# vco.net
KiCad netlist of a schematic drawn in EAGLE
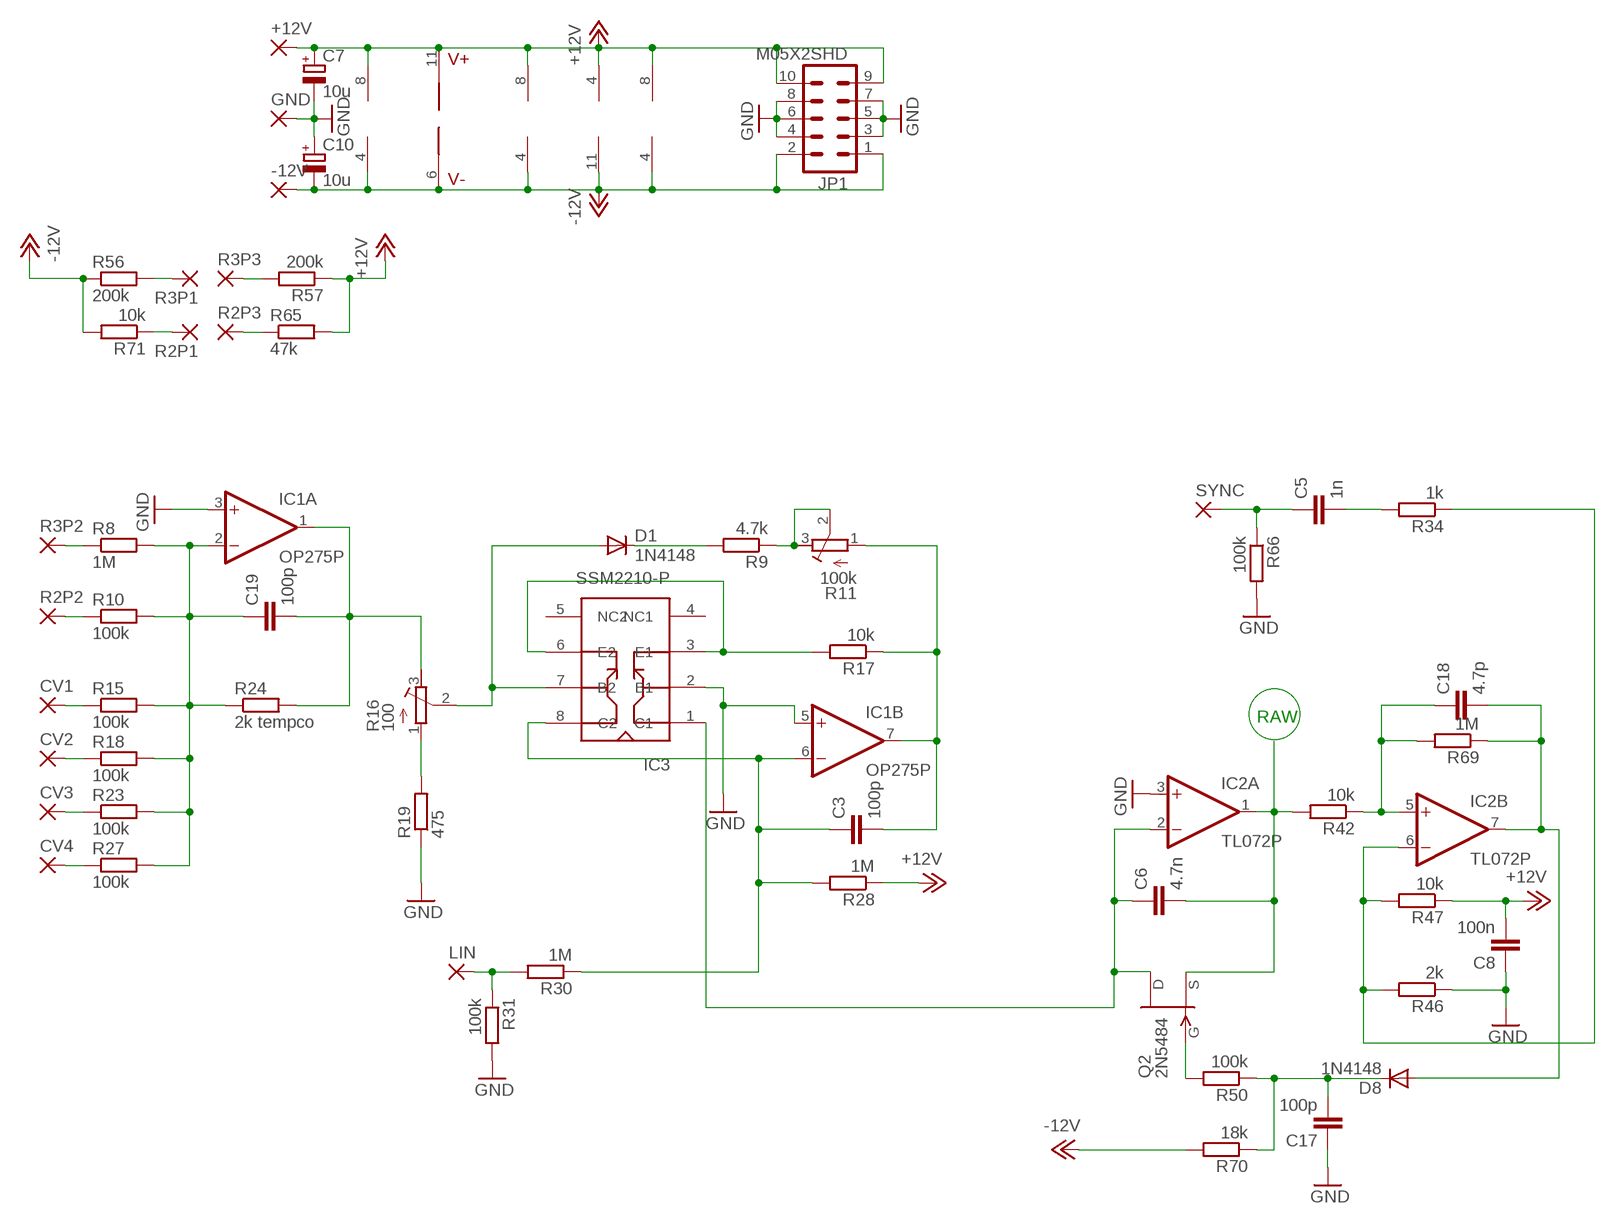
[diagram p0: schematic, sheet 1]
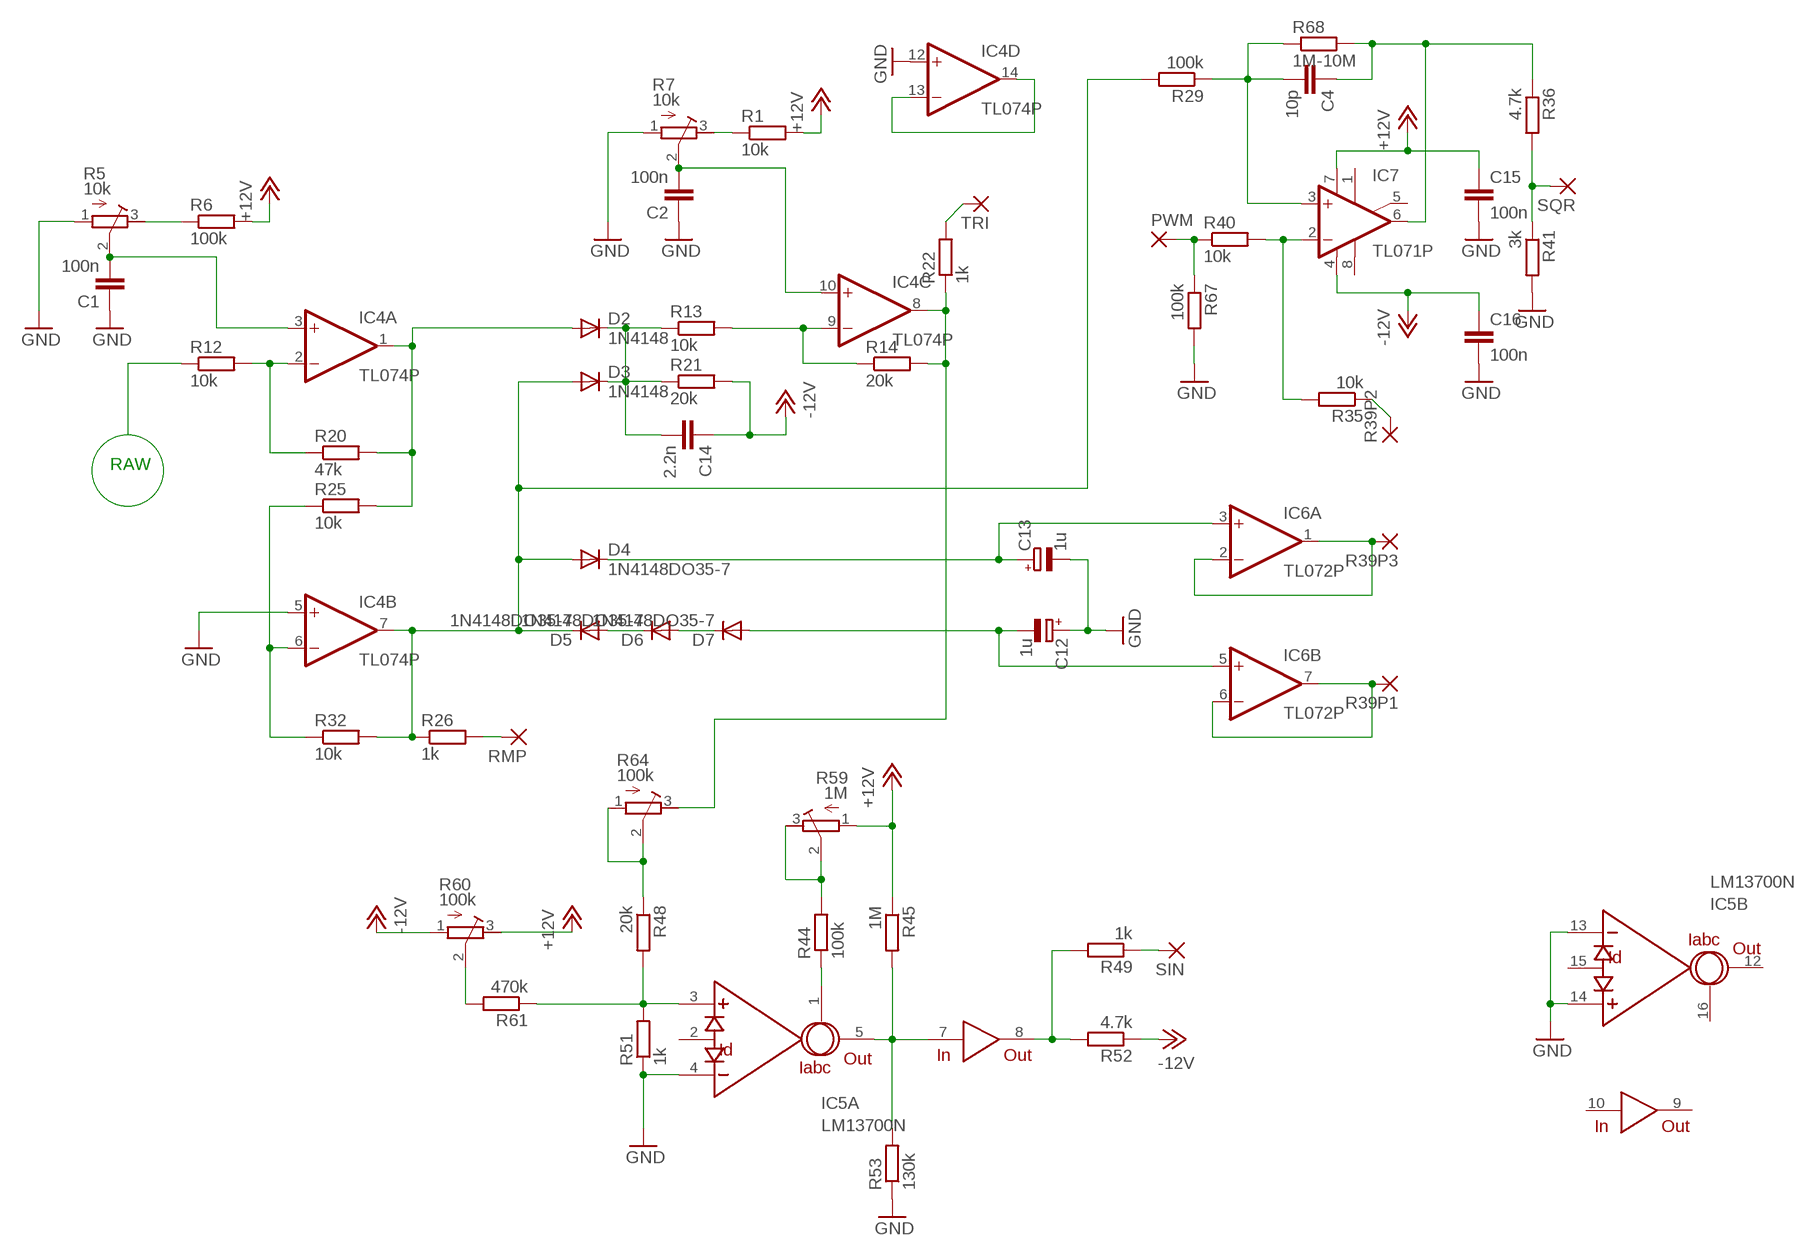
[diagram p1: schematic, sheet 2]

(export (version "E")
  (design (tool "Eeschema 10.0.6"))
  (components
    (comp (ref "C1")
      (value "100n")
      (footprint "eagle-import:C050-045X075")
      (libsource (lib "eagle-import") (part "C-EU050-045X075"))
    )
    (comp (ref "C2")
      (value "100n")
      (footprint "eagle-import:C050-045X075")
      (libsource (lib "eagle-import") (part "C-EU050-045X075"))
    )
    (comp (ref "C4")
      (value "10p")
      (footprint "eagle-import:C050-045X075")
      (libsource (lib "eagle-import") (part "C-EU050-045X075"))
    )
    (comp (ref "C12")
      (value "1u")
      (footprint "eagle-import:E2,5-7")
      (libsource (lib "eagle-import") (part "CPOL-EUE2.5-7"))
    )
    (comp (ref "C13")
      (value "1u")
      (footprint "eagle-import:E2,5-7")
      (libsource (lib "eagle-import") (part "CPOL-EUE2.5-7"))
    )
    (comp (ref "C14")
      (value "2.2n")
      (footprint "eagle-import:C050-045X075")
      (libsource (lib "eagle-import") (part "C-EU050-045X075"))
    )
    (comp (ref "C15")
      (value "100n")
      (footprint "eagle-import:C050-035X075")
      (libsource (lib "eagle-import") (part "C-EU050-035X075"))
    )
    (comp (ref "C16")
      (value "100n")
      (footprint "eagle-import:C050-035X075")
      (libsource (lib "eagle-import") (part "C-EU050-035X075"))
    )
    (comp (ref "D2")
      (value "1N4148")
      (footprint "eagle-import:DO35-7")
      (libsource (lib "eagle-import") (part "1N4148DO35-7"))
    )
    (comp (ref "D3")
      (value "1N4148")
      (footprint "eagle-import:DO35-7")
      (libsource (lib "eagle-import") (part "1N4148DO35-7"))
    )
    (comp (ref "D4")
      (value "1N4148DO35-7")
      (footprint "eagle-import:DO35-7")
      (libsource (lib "eagle-import") (part "1N4148DO35-7"))
    )
    (comp (ref "D5")
      (value "1N4148DO35-7")
      (footprint "eagle-import:DO35-7")
      (libsource (lib "eagle-import") (part "1N4148DO35-7"))
    )
    (comp (ref "D6")
      (value "1N4148DO35-7")
      (footprint "eagle-import:DO35-7")
      (libsource (lib "eagle-import") (part "1N4148DO35-7"))
    )
    (comp (ref "D7")
      (value "1N4148DO35-7")
      (footprint "eagle-import:DO35-7")
      (libsource (lib "eagle-import") (part "1N4148DO35-7"))
    )
    (comp (ref "IC4")
      (value "TL074P")
      (footprint "eagle-import:DIL14")
      (libsource (lib "eagle-import") (part "TL074P"))
    )
    (comp (ref "IC5")
      (value "LM13700N")
      (footprint "eagle-import:DIL16")
      (libsource (lib "eagle-import") (part "LM13700N"))
    )
    (comp (ref "IC6")
      (value "TL072P")
      (footprint "eagle-import:DIL08")
      (libsource (lib "eagle-import") (part "TL072P"))
    )
    (comp (ref "IC7")
      (value "TL071P")
      (footprint "eagle-import:DIL08")
      (libsource (lib "eagle-import") (part "TL071P"))
    )
    (comp (ref "PWM")
      (value "2,54/1,0")
      (footprint "eagle-import:2,54_1,0")
      (libsource (lib "eagle-import") (part "2,54/1,0"))
    )
    (comp (ref "R1")
      (value "10k")
      (footprint "eagle-import:0309V")
      (libsource (lib "eagle-import") (part "R-EU_0309/V"))
    )
    (comp (ref "R5")
      (value "10k")
      (footprint "eagle-import:RTRIM64W")
      (libsource (lib "eagle-import") (part "R-TRIMM64W"))
    )
    (comp (ref "R6")
      (value "100k")
      (footprint "eagle-import:0309V")
      (libsource (lib "eagle-import") (part "R-EU_0309/V"))
    )
    (comp (ref "R7")
      (value "10k")
      (footprint "eagle-import:RTRIM64W")
      (libsource (lib "eagle-import") (part "R-TRIMM64W"))
    )
    (comp (ref "R12")
      (value "10k")
      (footprint "eagle-import:0309V")
      (libsource (lib "eagle-import") (part "R-EU_0309/V"))
    )
    (comp (ref "R13")
      (value "10k")
      (footprint "eagle-import:0309_10")
      (libsource (lib "eagle-import") (part "R-EU_0309/10"))
    )
    (comp (ref "R14")
      (value "20k")
      (footprint "eagle-import:0309V")
      (libsource (lib "eagle-import") (part "R-EU_0309/V"))
    )
    (comp (ref "R20")
      (value "47k")
      (footprint "eagle-import:0309V")
      (libsource (lib "eagle-import") (part "R-EU_0309/V"))
    )
    (comp (ref "R21")
      (value "20k")
      (footprint "eagle-import:0309V")
      (libsource (lib "eagle-import") (part "R-EU_0309/V"))
    )
    (comp (ref "R22")
      (value "1k")
      (footprint "eagle-import:0309V")
      (libsource (lib "eagle-import") (part "R-EU_0309/V"))
    )
    (comp (ref "R25")
      (value "10k")
      (footprint "eagle-import:0309V")
      (libsource (lib "eagle-import") (part "R-EU_0309/V"))
    )
    (comp (ref "R26")
      (value "1k")
      (footprint "eagle-import:0309V")
      (libsource (lib "eagle-import") (part "R-EU_0309/V"))
    )
    (comp (ref "R29")
      (value "100k")
      (footprint "eagle-import:0309V")
      (libsource (lib "eagle-import") (part "R-EU_0309/V"))
    )
    (comp (ref "R32")
      (value "10k")
      (footprint "eagle-import:0309V")
      (libsource (lib "eagle-import") (part "R-EU_0309/V"))
    )
    (comp (ref "R35")
      (value "10k")
      (footprint "eagle-import:0309V")
      (libsource (lib "eagle-import") (part "R-EU_0309/V"))
    )
    (comp (ref "R36")
      (value "4.7k")
      (footprint "eagle-import:0309V")
      (libsource (lib "eagle-import") (part "R-EU_0309/V"))
    )
    (comp (ref "R39P1")
      (value "2,54/1,0")
      (footprint "eagle-import:2,54_1,0")
      (libsource (lib "eagle-import") (part "2,54/1,0"))
    )
    (comp (ref "R39P2")
      (value "2,54/1,0")
      (footprint "eagle-import:2,54_1,0")
      (libsource (lib "eagle-import") (part "2,54/1,0"))
    )
    (comp (ref "R39P3")
      (value "2,54/1,0")
      (footprint "eagle-import:2,54_1,0")
      (libsource (lib "eagle-import") (part "2,54/1,0"))
    )
    (comp (ref "R40")
      (value "10k")
      (footprint "eagle-import:0309V")
      (libsource (lib "eagle-import") (part "R-EU_0309/V"))
    )
    (comp (ref "R41")
      (value "3k")
      (footprint "eagle-import:0309V")
      (libsource (lib "eagle-import") (part "R-EU_0309/V"))
    )
    (comp (ref "R44")
      (value "100k")
      (footprint "eagle-import:0309V")
      (libsource (lib "eagle-import") (part "R-EU_0309/V"))
    )
    (comp (ref "R45")
      (value "1M")
      (footprint "eagle-import:0309V")
      (libsource (lib "eagle-import") (part "R-EU_0309/V"))
    )
    (comp (ref "R48")
      (value "20k")
      (footprint "eagle-import:0309V")
      (libsource (lib "eagle-import") (part "R-EU_0309/V"))
    )
    (comp (ref "R49")
      (value "1k")
      (footprint "eagle-import:0309V")
      (libsource (lib "eagle-import") (part "R-EU_0309/V"))
    )
    (comp (ref "R51")
      (value "1k")
      (footprint "eagle-import:0309V")
      (libsource (lib "eagle-import") (part "R-EU_0309/V"))
    )
    (comp (ref "R52")
      (value "4.7k")
      (footprint "eagle-import:0309V")
      (libsource (lib "eagle-import") (part "R-EU_0309/V"))
    )
    (comp (ref "R53")
      (value "130k")
      (footprint "eagle-import:0309V")
      (libsource (lib "eagle-import") (part "R-EU_0309/V"))
    )
    (comp (ref "R59")
      (value "1M")
      (footprint "eagle-import:RTRIM64W")
      (libsource (lib "eagle-import") (part "R-TRIMM64W"))
    )
    (comp (ref "R60")
      (value "100k")
      (footprint "eagle-import:RTRIM64W")
      (libsource (lib "eagle-import") (part "R-TRIMM64W"))
    )
    (comp (ref "R61")
      (value "470k")
      (footprint "eagle-import:0309V")
      (libsource (lib "eagle-import") (part "R-EU_0309/V"))
    )
    (comp (ref "R64")
      (value "100k")
      (footprint "eagle-import:RTRIM64W")
      (libsource (lib "eagle-import") (part "R-TRIMM64W"))
    )
    (comp (ref "R67")
      (value "100k")
      (footprint "eagle-import:0309V")
      (libsource (lib "eagle-import") (part "R-EU_0309/V"))
    )
    (comp (ref "R68")
      (value "1M-10M")
      (footprint "eagle-import:0309V")
      (libsource (lib "eagle-import") (part "R-EU_0309/V"))
    )
    (comp (ref "RMP")
      (value "2,54/1,0")
      (footprint "eagle-import:2,54_1,0")
      (libsource (lib "eagle-import") (part "2,54/1,0"))
    )
    (comp (ref "SIN")
      (value "2,54/1,0")
      (footprint "eagle-import:2,54_1,0")
      (libsource (lib "eagle-import") (part "2,54/1,0"))
    )
    (comp (ref "SQR")
      (value "2,54/1,0")
      (footprint "eagle-import:2,54_1,0")
      (libsource (lib "eagle-import") (part "2,54/1,0"))
    )
    (comp (ref "TRI")
      (value "2,54/1,0")
      (footprint "eagle-import:2,54_1,0")
      (libsource (lib "eagle-import") (part "2,54/1,0"))
    )
    (comp (ref "+12V")
      (value "2,54/1,0")
      (footprint "eagle-import:2,54_1,0")
      (libsource (lib "eagle-import") (part "2,54/1,0"))
    )
    (comp (ref "-12V")
      (value "2,54/1,0")
      (footprint "eagle-import:2,54_1,0")
      (libsource (lib "eagle-import") (part "2,54/1,0"))
    )
    (comp (ref "C3")
      (value "100p")
      (footprint "eagle-import:C050-045X075")
      (libsource (lib "eagle-import") (part "C-EU050-045X075"))
    )
    (comp (ref "C5")
      (value "1n")
      (footprint "eagle-import:C050-045X075")
      (libsource (lib "eagle-import") (part "C-EU050-045X075"))
    )
    (comp (ref "C6")
      (value "4.7n")
      (footprint "eagle-import:C050-045X075")
      (libsource (lib "eagle-import") (part "C-EU050-045X075"))
    )
    (comp (ref "C7")
      (value "10u")
      (footprint "eagle-import:E2,5-7")
      (libsource (lib "eagle-import") (part "CPOL-EUE2.5-7"))
    )
    (comp (ref "C8")
      (value "100n")
      (footprint "eagle-import:C050-045X075")
      (libsource (lib "eagle-import") (part "C-EU050-045X075"))
    )
    (comp (ref "C10")
      (value "10u")
      (footprint "eagle-import:E2,5-7")
      (libsource (lib "eagle-import") (part "CPOL-EUE2.5-7"))
    )
    (comp (ref "C17")
      (value "100p")
      (footprint "eagle-import:C050-045X075")
      (libsource (lib "eagle-import") (part "C-EU050-045X075"))
    )
    (comp (ref "C18")
      (value "4.7p")
      (footprint "eagle-import:C050-045X075")
      (libsource (lib "eagle-import") (part "C-EU050-045X075"))
    )
    (comp (ref "C19")
      (value "100p")
      (footprint "eagle-import:C050-045X075")
      (libsource (lib "eagle-import") (part "C-EU050-045X075"))
    )
    (comp (ref "CV1")
      (value "2,54/1,0")
      (footprint "eagle-import:2,54_1,0")
      (libsource (lib "eagle-import") (part "2,54/1,0"))
    )
    (comp (ref "CV2")
      (value "2,54/1,0")
      (footprint "eagle-import:2,54_1,0")
      (libsource (lib "eagle-import") (part "2,54/1,0"))
    )
    (comp (ref "CV3")
      (value "2,54/1,0")
      (footprint "eagle-import:2,54_1,0")
      (libsource (lib "eagle-import") (part "2,54/1,0"))
    )
    (comp (ref "CV4")
      (value "2,54/1,0")
      (footprint "eagle-import:2,54_1,0")
      (libsource (lib "eagle-import") (part "2,54/1,0"))
    )
    (comp (ref "D1")
      (value "1N4148")
      (footprint "eagle-import:DO35-7")
      (libsource (lib "eagle-import") (part "1N4148DO35-7"))
    )
    (comp (ref "D8")
      (value "1N4148")
      (footprint "eagle-import:DO35-7")
      (libsource (lib "eagle-import") (part "1N4148DO35-7"))
    )
    (comp (ref "GND")
      (value "2,54/1,0")
      (footprint "eagle-import:2,54_1,0")
      (libsource (lib "eagle-import") (part "2,54/1,0"))
    )
    (comp (ref "IC1")
      (value "OP275P")
      (footprint "eagle-import:DIL08")
      (libsource (lib "eagle-import") (part "OP275P"))
    )
    (comp (ref "IC2")
      (value "TL072P")
      (footprint "eagle-import:DIL08")
      (libsource (lib "eagle-import") (part "TL072P"))
    )
    (comp (ref "IC3")
      (value "SSM2210-P")
      (footprint "eagle-import:DIL08")
      (libsource (lib "eagle-import") (part "SSM2210-P"))
    )
    (comp (ref "JP1")
      (value "M05X2SHD")
      (footprint "eagle-import:2X5-SHROUDED")
      (libsource (lib "eagle-import") (part "M05X2SHD"))
    )
    (comp (ref "LIN")
      (value "2,54/1,0")
      (footprint "eagle-import:2,54_1,0")
      (libsource (lib "eagle-import") (part "2,54/1,0"))
    )
    (comp (ref "Q2")
      (value "2N5484")
      (footprint "eagle-import:TO92-")
      (libsource (lib "eagle-import") (part "?5482N4"))
    )
    (comp (ref "R2P1")
      (value "2,54/1,0")
      (footprint "eagle-import:2,54_1,0")
      (libsource (lib "eagle-import") (part "2,54/1,0"))
    )
    (comp (ref "R2P2")
      (value "2,54/1,0")
      (footprint "eagle-import:2,54_1,0")
      (libsource (lib "eagle-import") (part "2,54/1,0"))
    )
    (comp (ref "R2P3")
      (value "2,54/1,0")
      (footprint "eagle-import:2,54_1,0")
      (libsource (lib "eagle-import") (part "2,54/1,0"))
    )
    (comp (ref "R3P1")
      (value "2,54/1,0")
      (footprint "eagle-import:2,54_1,0")
      (libsource (lib "eagle-import") (part "2,54/1,0"))
    )
    (comp (ref "R3P2")
      (value "2,54/1,0")
      (footprint "eagle-import:2,54_1,0")
      (libsource (lib "eagle-import") (part "2,54/1,0"))
    )
    (comp (ref "R3P3")
      (value "2,54/1,0")
      (footprint "eagle-import:2,54_1,0")
      (libsource (lib "eagle-import") (part "2,54/1,0"))
    )
    (comp (ref "R8")
      (value "1M")
      (footprint "eagle-import:0309V")
      (libsource (lib "eagle-import") (part "R-EU_0309/V"))
    )
    (comp (ref "R9")
      (value "4.7k")
      (footprint "eagle-import:0309V")
      (libsource (lib "eagle-import") (part "R-EU_0309/V"))
    )
    (comp (ref "R10")
      (value "100k")
      (footprint "eagle-import:0309V")
      (libsource (lib "eagle-import") (part "R-EU_0309/V"))
    )
    (comp (ref "R11")
      (value "100k")
      (footprint "eagle-import:RTRIM64W")
      (libsource (lib "eagle-import") (part "R-TRIMM64W"))
    )
    (comp (ref "R15")
      (value "100k")
      (footprint "eagle-import:0309V")
      (libsource (lib "eagle-import") (part "R-EU_0309/V"))
    )
    (comp (ref "R16")
      (value "100")
      (footprint "eagle-import:RTRIM64W")
      (libsource (lib "eagle-import") (part "R-TRIMM64W"))
    )
    (comp (ref "R17")
      (value "10k")
      (footprint "eagle-import:0309V")
      (libsource (lib "eagle-import") (part "R-EU_0309/V"))
    )
    (comp (ref "R18")
      (value "100k")
      (footprint "eagle-import:0309V")
      (libsource (lib "eagle-import") (part "R-EU_0309/V"))
    )
    (comp (ref "R19")
      (value "475")
      (footprint "eagle-import:0309V")
      (libsource (lib "eagle-import") (part "R-EU_0309/V"))
    )
    (comp (ref "R23")
      (value "100k")
      (footprint "eagle-import:0309V")
      (libsource (lib "eagle-import") (part "R-EU_0309/V"))
    )
    (comp (ref "R24")
      (value "2k tempco")
      (footprint "eagle-import:0309_12")
      (libsource (lib "eagle-import") (part "R-EU_0309/12"))
    )
    (comp (ref "R27")
      (value "100k")
      (footprint "eagle-import:0309V")
      (libsource (lib "eagle-import") (part "R-EU_0309/V"))
    )
    (comp (ref "R28")
      (value "1M")
      (footprint "eagle-import:0309V")
      (libsource (lib "eagle-import") (part "R-EU_0309/V"))
    )
    (comp (ref "R30")
      (value "1M")
      (footprint "eagle-import:0309V")
      (libsource (lib "eagle-import") (part "R-EU_0309/V"))
    )
    (comp (ref "R31")
      (value "100k")
      (footprint "eagle-import:0309V")
      (libsource (lib "eagle-import") (part "R-EU_0309/V"))
    )
    (comp (ref "R34")
      (value "1k")
      (footprint "eagle-import:0309V")
      (libsource (lib "eagle-import") (part "R-EU_0309/V"))
    )
    (comp (ref "R42")
      (value "10k")
      (footprint "eagle-import:0309V")
      (libsource (lib "eagle-import") (part "R-EU_0309/V"))
    )
    (comp (ref "R46")
      (value "2k")
      (footprint "eagle-import:0309V")
      (libsource (lib "eagle-import") (part "R-EU_0309/V"))
    )
    (comp (ref "R47")
      (value "10k")
      (footprint "eagle-import:0309V")
      (libsource (lib "eagle-import") (part "R-EU_0309/V"))
    )
    (comp (ref "R50")
      (value "100k")
      (footprint "eagle-import:0309V")
      (libsource (lib "eagle-import") (part "R-EU_0309/V"))
    )
    (comp (ref "R56")
      (value "200k")
      (footprint "eagle-import:0309V")
      (libsource (lib "eagle-import") (part "R-EU_0309/V"))
    )
    (comp (ref "R57")
      (value "200k")
      (footprint "eagle-import:0309V")
      (libsource (lib "eagle-import") (part "R-EU_0309/V"))
    )
    (comp (ref "R65")
      (value "47k")
      (footprint "eagle-import:0309V")
      (libsource (lib "eagle-import") (part "R-EU_0309/V"))
    )
    (comp (ref "R66")
      (value "100k")
      (footprint "eagle-import:0309V")
      (libsource (lib "eagle-import") (part "R-EU_0309/V"))
    )
    (comp (ref "R69")
      (value "1M")
      (footprint "eagle-import:0309V")
      (libsource (lib "eagle-import") (part "R-EU_0309/V"))
    )
    (comp (ref "R70")
      (value "18k")
      (footprint "eagle-import:0309V")
      (libsource (lib "eagle-import") (part "R-EU_0309/V"))
    )
    (comp (ref "R71")
      (value "10k")
      (footprint "eagle-import:0309V")
      (libsource (lib "eagle-import") (part "R-EU_0309/V"))
    )
    (comp (ref "SYNC")
      (value "2,54/1,0")
      (footprint "eagle-import:2,54_1,0")
      (libsource (lib "eagle-import") (part "2,54/1,0"))
    )
  )
  (nets
    (net (code "1") (name "+12V") (class "Default")
      (node (ref "+12V") (pin "1") (pinfunction "P_1") (pintype "passive"))
      (node (ref "C15") (pin "1") (pinfunction "1_1") (pintype "passive"))
      (node (ref "C7") (pin "+") (pinfunction "+_+") (pintype "passive"))
      (node (ref "C8") (pin "2") (pinfunction "2_2") (pintype "passive"))
      (node (ref "IC1") (pin "8") (pinfunction "V+_8") (pintype "power_in"))
      (node (ref "IC2") (pin "8") (pinfunction "V+_8") (pintype "power_in"))
      (node (ref "IC4") (pin "4") (pinfunction "V+_4") (pintype "power_in"))
      (node (ref "IC5") (pin "11") (pinfunction "V+_11") (pintype "bidirectional"))
      (node (ref "IC6") (pin "8") (pinfunction "V+_8") (pintype "power_in"))
      (node (ref "IC7") (pin "7") (pinfunction "V+_7") (pintype "power_in"))
      (node (ref "JP1") (pin "10") (pinfunction "10_10") (pintype "passive"))
      (node (ref "JP1") (pin "9") (pinfunction "9_9") (pintype "passive"))
      (node (ref "R1") (pin "2") (pinfunction "2_2") (pintype "passive"))
      (node (ref "R28") (pin "1") (pinfunction "1_1") (pintype "passive"))
      (node (ref "R45") (pin "1") (pinfunction "1_1") (pintype "passive"))
      (node (ref "R47") (pin "1") (pinfunction "1_1") (pintype "passive"))
      (node (ref "R57") (pin "1") (pinfunction "1_1") (pintype "passive"))
      (node (ref "R59") (pin "1") (pinfunction "A_1") (pintype "passive"))
      (node (ref "R6") (pin "2") (pinfunction "2_2") (pintype "passive"))
      (node (ref "R60") (pin "3") (pinfunction "E_3") (pintype "passive"))
      (node (ref "R65") (pin "2") (pinfunction "2_2") (pintype "passive"))
    )
    (net (code "2") (name "-12V") (class "Default")
      (node (ref "-12V") (pin "1") (pinfunction "P_1") (pintype "passive"))
      (node (ref "C10") (pin "-") (pinfunction "-_-") (pintype "passive"))
      (node (ref "C14") (pin "1") (pinfunction "1_1") (pintype "passive"))
      (node (ref "C16") (pin "1") (pinfunction "1_1") (pintype "passive"))
      (node (ref "IC1") (pin "4") (pinfunction "V-_4") (pintype "power_in"))
      (node (ref "IC2") (pin "4") (pinfunction "V-_4") (pintype "power_in"))
      (node (ref "IC4") (pin "11") (pinfunction "V-_11") (pintype "power_in"))
      (node (ref "IC5") (pin "6") (pinfunction "V-_6") (pintype "bidirectional"))
      (node (ref "IC6") (pin "4") (pinfunction "V-_4") (pintype "power_in"))
      (node (ref "IC7") (pin "4") (pinfunction "V-_4") (pintype "power_in"))
      (node (ref "JP1") (pin "1") (pinfunction "1_1") (pintype "passive"))
      (node (ref "JP1") (pin "2") (pinfunction "2_2") (pintype "passive"))
      (node (ref "R21") (pin "2") (pinfunction "2_2") (pintype "passive"))
      (node (ref "R52") (pin "1") (pinfunction "1_1") (pintype "passive"))
      (node (ref "R56") (pin "1") (pinfunction "1_1") (pintype "passive"))
      (node (ref "R60") (pin "1") (pinfunction "A_1") (pintype "passive"))
      (node (ref "R70") (pin "2") (pinfunction "2_2") (pintype "passive"))
      (node (ref "R71") (pin "2") (pinfunction "2_2") (pintype "passive"))
    )
    (net (code "3") (name "GND") (class "Default")
      (node (ref "C1") (pin "1") (pinfunction "1_1") (pintype "passive"))
      (node (ref "C10") (pin "+") (pinfunction "+_+") (pintype "passive"))
      (node (ref "C12") (pin "+") (pinfunction "+_+") (pintype "passive"))
      (node (ref "C13") (pin "-") (pinfunction "-_-") (pintype "passive"))
      (node (ref "C15") (pin "2") (pinfunction "2_2") (pintype "passive"))
      (node (ref "C16") (pin "2") (pinfunction "2_2") (pintype "passive"))
      (node (ref "C17") (pin "1") (pinfunction "1_1") (pintype "passive"))
      (node (ref "C2") (pin "1") (pinfunction "1_1") (pintype "passive"))
      (node (ref "C7") (pin "-") (pinfunction "-_-") (pintype "passive"))
      (node (ref "C8") (pin "1") (pinfunction "1_1") (pintype "passive"))
      (node (ref "GND") (pin "1") (pinfunction "P_1") (pintype "passive"))
      (node (ref "IC1") (pin "3") (pinfunction "+IN_3") (pintype "input"))
      (node (ref "IC1") (pin "5") (pinfunction "+IN_5") (pintype "input"))
      (node (ref "IC2") (pin "3") (pinfunction "+IN_3") (pintype "input"))
      (node (ref "IC3") (pin "2") (pinfunction "B1_2") (pintype "bidirectional"))
      (node (ref "IC4") (pin "12") (pinfunction "+IN_12") (pintype "input"))
      (node (ref "IC4") (pin "5") (pinfunction "+IN_5") (pintype "input"))
      (node (ref "IC5") (pin "13") (pinfunction "-IN_13") (pintype "bidirectional"))
      (node (ref "IC5") (pin "14") (pinfunction "+IN_14") (pintype "bidirectional"))
      (node (ref "IC5") (pin "4") (pinfunction "-IN_4") (pintype "bidirectional"))
      (node (ref "JP1") (pin "3") (pinfunction "3_3") (pintype "passive"))
      (node (ref "JP1") (pin "4") (pinfunction "4_4") (pintype "passive"))
      (node (ref "JP1") (pin "5") (pinfunction "5_5") (pintype "passive"))
      (node (ref "JP1") (pin "6") (pinfunction "6_6") (pintype "passive"))
      (node (ref "JP1") (pin "7") (pinfunction "7_7") (pintype "passive"))
      (node (ref "JP1") (pin "8") (pinfunction "8_8") (pintype "passive"))
      (node (ref "R19") (pin "1") (pinfunction "1_1") (pintype "passive"))
      (node (ref "R31") (pin "2") (pinfunction "2_2") (pintype "passive"))
      (node (ref "R41") (pin "2") (pinfunction "2_2") (pintype "passive"))
      (node (ref "R46") (pin "1") (pinfunction "1_1") (pintype "passive"))
      (node (ref "R5") (pin "1") (pinfunction "A_1") (pintype "passive"))
      (node (ref "R51") (pin "1") (pinfunction "1_1") (pintype "passive"))
      (node (ref "R53") (pin "1") (pinfunction "1_1") (pintype "passive"))
      (node (ref "R66") (pin "2") (pinfunction "2_2") (pintype "passive"))
      (node (ref "R67") (pin "2") (pinfunction "2_2") (pintype "passive"))
      (node (ref "R7") (pin "1") (pinfunction "A_1") (pintype "passive"))
    )
    (net (code "4") (name "Net-(C5-Pad2)") (class "Default")
      (node (ref "C5") (pin "2") (pinfunction "2_2") (pintype "passive"))
      (node (ref "R34") (pin "2") (pinfunction "2_2") (pintype "passive"))
    )
    (net (code "5") (name "Net-(C14-Pad2)") (class "Default")
      (node (ref "C14") (pin "2") (pinfunction "2_2") (pintype "passive"))
      (node (ref "D2") (pin "C") (pinfunction "C_C") (pintype "passive"))
      (node (ref "D3") (pin "C") (pinfunction "C_C") (pintype "passive"))
      (node (ref "R13") (pin "1") (pinfunction "1_1") (pintype "passive"))
      (node (ref "R21") (pin "1") (pinfunction "1_1") (pintype "passive"))
    )
    (net (code "6") (name "Net-(C17-Pad2)") (class "Default")
      (node (ref "C17") (pin "2") (pinfunction "2_2") (pintype "passive"))
      (node (ref "D8") (pin "C") (pinfunction "C_C") (pintype "passive"))
      (node (ref "R50") (pin "1") (pinfunction "1_1") (pintype "passive"))
      (node (ref "R70") (pin "1") (pinfunction "1_1") (pintype "passive"))
    )
    (net (code "7") (name "Net-(CV1-P)") (class "Default")
      (node (ref "CV1") (pin "1") (pinfunction "P_1") (pintype "passive"))
      (node (ref "R15") (pin "1") (pinfunction "1_1") (pintype "passive"))
    )
    (net (code "8") (name "Net-(CV2-P)") (class "Default")
      (node (ref "CV2") (pin "1") (pinfunction "P_1") (pintype "passive"))
      (node (ref "R18") (pin "1") (pinfunction "1_1") (pintype "passive"))
    )
    (net (code "9") (name "Net-(CV3-P)") (class "Default")
      (node (ref "CV3") (pin "1") (pinfunction "P_1") (pintype "passive"))
      (node (ref "R23") (pin "1") (pinfunction "1_1") (pintype "passive"))
    )
    (net (code "10") (name "Net-(CV4-P)") (class "Default")
      (node (ref "CV4") (pin "1") (pinfunction "P_1") (pintype "passive"))
      (node (ref "R27") (pin "1") (pinfunction "1_1") (pintype "passive"))
    )
    (net (code "11") (name "Net-(D1-PadC)") (class "Default")
      (node (ref "D1") (pin "C") (pinfunction "C_C") (pintype "passive"))
      (node (ref "R9") (pin "2") (pinfunction "2_2") (pintype "passive"))
    )
    (net (code "12") (name "Net-(D5-PadA)") (class "Default")
      (node (ref "D5") (pin "A") (pinfunction "A_A") (pintype "passive"))
      (node (ref "D6") (pin "C") (pinfunction "C_C") (pintype "passive"))
    )
    (net (code "13") (name "Net-(D6-PadA)") (class "Default")
      (node (ref "D6") (pin "A") (pinfunction "A_A") (pintype "passive"))
      (node (ref "D7") (pin "C") (pinfunction "C_C") (pintype "passive"))
    )
    (net (code "14") (name "Net-(IC1A--IN)") (class "Default")
      (node (ref "C19") (pin "1") (pinfunction "1_1") (pintype "passive"))
      (node (ref "IC1") (pin "2") (pinfunction "-IN_2") (pintype "input"))
      (node (ref "R10") (pin "2") (pinfunction "2_2") (pintype "passive"))
      (node (ref "R15") (pin "2") (pinfunction "2_2") (pintype "passive"))
      (node (ref "R18") (pin "2") (pinfunction "2_2") (pintype "passive"))
      (node (ref "R23") (pin "2") (pinfunction "2_2") (pintype "passive"))
      (node (ref "R24") (pin "1") (pinfunction "1_1") (pintype "passive"))
      (node (ref "R27") (pin "2") (pinfunction "2_2") (pintype "passive"))
      (node (ref "R8") (pin "2") (pinfunction "2_2") (pintype "passive"))
    )
    (net (code "15") (name "Net-(IC1A-OUT)") (class "Default")
      (node (ref "C19") (pin "2") (pinfunction "2_2") (pintype "passive"))
      (node (ref "IC1") (pin "1") (pinfunction "OUT_1") (pintype "output"))
      (node (ref "R16") (pin "3") (pinfunction "E_3") (pintype "passive"))
      (node (ref "R24") (pin "2") (pinfunction "2_2") (pintype "passive"))
    )
    (net (code "16") (name "Net-(IC1B--IN)") (class "Default")
      (node (ref "C3") (pin "1") (pinfunction "1_1") (pintype "passive"))
      (node (ref "IC1") (pin "6") (pinfunction "-IN_6") (pintype "input"))
      (node (ref "IC3") (pin "8") (pinfunction "C2_8") (pintype "bidirectional"))
      (node (ref "R28") (pin "2") (pinfunction "2_2") (pintype "passive"))
      (node (ref "R30") (pin "1") (pinfunction "1_1") (pintype "passive"))
    )
    (net (code "17") (name "Net-(IC1B-OUT)") (class "Default")
      (node (ref "C3") (pin "2") (pinfunction "2_2") (pintype "passive"))
      (node (ref "IC1") (pin "7") (pinfunction "OUT_7") (pintype "output"))
      (node (ref "R11") (pin "1") (pinfunction "A_1") (pintype "passive"))
      (node (ref "R17") (pin "1") (pinfunction "1_1") (pintype "passive"))
    )
    (net (code "18") (name "Net-(IC2A--IN)") (class "Default")
      (node (ref "C6") (pin "1") (pinfunction "1_1") (pintype "passive"))
      (node (ref "IC2") (pin "2") (pinfunction "-IN_2") (pintype "input"))
      (node (ref "IC3") (pin "1") (pinfunction "C1_1") (pintype "bidirectional"))
      (node (ref "Q2") (pin "3") (pinfunction "D_3") (pintype "passive"))
    )
    (net (code "19") (name "Net-(IC2B-+IN)") (class "Default")
      (node (ref "C18") (pin "1") (pinfunction "1_1") (pintype "passive"))
      (node (ref "IC2") (pin "5") (pinfunction "+IN_5") (pintype "input"))
      (node (ref "R42") (pin "1") (pinfunction "1_1") (pintype "passive"))
      (node (ref "R69") (pin "2") (pinfunction "2_2") (pintype "passive"))
    )
    (net (code "20") (name "Net-(IC2B--IN)") (class "Default")
      (node (ref "IC2") (pin "6") (pinfunction "-IN_6") (pintype "input"))
      (node (ref "R34") (pin "1") (pinfunction "1_1") (pintype "passive"))
      (node (ref "R46") (pin "2") (pinfunction "2_2") (pintype "passive"))
      (node (ref "R47") (pin "2") (pinfunction "2_2") (pintype "passive"))
    )
    (net (code "21") (name "Net-(IC2B-OUT)") (class "Default")
      (node (ref "C18") (pin "2") (pinfunction "2_2") (pintype "passive"))
      (node (ref "D8") (pin "A") (pinfunction "A_A") (pintype "passive"))
      (node (ref "IC2") (pin "7") (pinfunction "OUT_7") (pintype "output"))
      (node (ref "R69") (pin "1") (pinfunction "1_1") (pintype "passive"))
    )
    (net (code "22") (name "Net-(IC3-B2)") (class "Default")
      (node (ref "D1") (pin "A") (pinfunction "A_A") (pintype "passive"))
      (node (ref "IC3") (pin "7") (pinfunction "B2_7") (pintype "bidirectional"))
      (node (ref "R16") (pin "2") (pinfunction "S_2") (pintype "passive"))
    )
    (net (code "23") (name "Net-(IC3-E1)") (class "Default")
      (node (ref "IC3") (pin "3") (pinfunction "E1_3") (pintype "bidirectional"))
      (node (ref "IC3") (pin "6") (pinfunction "E2_6") (pintype "bidirectional"))
      (node (ref "R17") (pin "2") (pinfunction "2_2") (pintype "passive"))
    )
    (net (code "24") (name "Net-(IC4A-+IN)") (class "Default")
      (node (ref "C1") (pin "2") (pinfunction "2_2") (pintype "passive"))
      (node (ref "IC4") (pin "3") (pinfunction "+IN_3") (pintype "input"))
      (node (ref "R5") (pin "2") (pinfunction "S_2") (pintype "passive"))
    )
    (net (code "25") (name "Net-(IC4A--IN)") (class "Default")
      (node (ref "IC4") (pin "2") (pinfunction "-IN_2") (pintype "input"))
      (node (ref "R12") (pin "2") (pinfunction "2_2") (pintype "passive"))
      (node (ref "R20") (pin "1") (pinfunction "1_1") (pintype "passive"))
    )
    (net (code "26") (name "Net-(IC4A-OUT)") (class "Default")
      (node (ref "D2") (pin "A") (pinfunction "A_A") (pintype "passive"))
      (node (ref "IC4") (pin "1") (pinfunction "OUT_1") (pintype "output"))
      (node (ref "R20") (pin "2") (pinfunction "2_2") (pintype "passive"))
      (node (ref "R25") (pin "2") (pinfunction "2_2") (pintype "passive"))
    )
    (net (code "27") (name "Net-(IC4B--IN)") (class "Default")
      (node (ref "IC4") (pin "6") (pinfunction "-IN_6") (pintype "input"))
      (node (ref "R25") (pin "1") (pinfunction "1_1") (pintype "passive"))
      (node (ref "R32") (pin "1") (pinfunction "1_1") (pintype "passive"))
    )
    (net (code "28") (name "Net-(IC4B-OUT)") (class "Default")
      (node (ref "D3") (pin "A") (pinfunction "A_A") (pintype "passive"))
      (node (ref "D4") (pin "A") (pinfunction "A_A") (pintype "passive"))
      (node (ref "D5") (pin "C") (pinfunction "C_C") (pintype "passive"))
      (node (ref "IC4") (pin "7") (pinfunction "OUT_7") (pintype "output"))
      (node (ref "R26") (pin "1") (pinfunction "1_1") (pintype "passive"))
      (node (ref "R29") (pin "2") (pinfunction "2_2") (pintype "passive"))
      (node (ref "R32") (pin "2") (pinfunction "2_2") (pintype "passive"))
    )
    (net (code "29") (name "Net-(IC4C-+IN)") (class "Default")
      (node (ref "C2") (pin "2") (pinfunction "2_2") (pintype "passive"))
      (node (ref "IC4") (pin "10") (pinfunction "+IN_10") (pintype "input"))
      (node (ref "R7") (pin "2") (pinfunction "S_2") (pintype "passive"))
    )
    (net (code "30") (name "Net-(IC4C--IN)") (class "Default")
      (node (ref "IC4") (pin "9") (pinfunction "-IN_9") (pintype "input"))
      (node (ref "R13") (pin "2") (pinfunction "2_2") (pintype "passive"))
      (node (ref "R14") (pin "1") (pinfunction "1_1") (pintype "passive"))
    )
    (net (code "31") (name "Net-(IC4C-OUT)") (class "Default")
      (node (ref "IC4") (pin "8") (pinfunction "OUT_8") (pintype "output"))
      (node (ref "R14") (pin "2") (pinfunction "2_2") (pintype "passive"))
      (node (ref "R22") (pin "1") (pinfunction "1_1") (pintype "passive"))
      (node (ref "R64") (pin "3") (pinfunction "E_3") (pintype "passive"))
    )
    (net (code "32") (name "Net-(IC4D--IN)") (class "Default")
      (node (ref "IC4") (pin "13") (pinfunction "-IN_13") (pintype "input"))
      (node (ref "IC4") (pin "14") (pinfunction "OUT_14") (pintype "output"))
    )
    (net (code "33") (name "Net-(IC5A-+IN)") (class "Default")
      (node (ref "IC5") (pin "3") (pinfunction "+IN_3") (pintype "bidirectional"))
      (node (ref "R48") (pin "2") (pinfunction "2_2") (pintype "passive"))
      (node (ref "R51") (pin "2") (pinfunction "2_2") (pintype "passive"))
      (node (ref "R61") (pin "1") (pinfunction "1_1") (pintype "passive"))
    )
    (net (code "34") (name "Net-(IC5A-IABC)") (class "Default")
      (node (ref "IC5") (pin "1") (pinfunction "IABC_1") (pintype "bidirectional"))
      (node (ref "R44") (pin "1") (pinfunction "1_1") (pintype "passive"))
    )
    (net (code "35") (name "Net-(IC5A-OUT)") (class "Default")
      (node (ref "IC5") (pin "5") (pinfunction "OUT_5") (pintype "bidirectional"))
      (node (ref "IC5") (pin "7") (pinfunction "IN_7") (pintype "bidirectional"))
      (node (ref "R45") (pin "2") (pinfunction "2_2") (pintype "passive"))
      (node (ref "R53") (pin "2") (pinfunction "2_2") (pintype "passive"))
    )
    (net (code "36") (name "Net-(IC5C-OUT)") (class "Default")
      (node (ref "IC5") (pin "8") (pinfunction "OUT_8") (pintype "bidirectional"))
      (node (ref "R49") (pin "2") (pinfunction "2_2") (pintype "passive"))
      (node (ref "R52") (pin "2") (pinfunction "2_2") (pintype "passive"))
    )
    (net (code "37") (name "Net-(IC6A-+IN)") (class "Default")
      (node (ref "C13") (pin "+") (pinfunction "+_+") (pintype "passive"))
      (node (ref "D4") (pin "C") (pinfunction "C_C") (pintype "passive"))
      (node (ref "IC6") (pin "3") (pinfunction "+IN_3") (pintype "input"))
    )
    (net (code "38") (name "Net-(IC6A--IN)") (class "Default")
      (node (ref "IC6") (pin "1") (pinfunction "OUT_1") (pintype "output"))
      (node (ref "IC6") (pin "2") (pinfunction "-IN_2") (pintype "input"))
      (node (ref "R39P3") (pin "1") (pinfunction "P_1") (pintype "passive"))
    )
    (net (code "39") (name "Net-(IC6B-+IN)") (class "Default")
      (node (ref "C12") (pin "-") (pinfunction "-_-") (pintype "passive"))
      (node (ref "D7") (pin "A") (pinfunction "A_A") (pintype "passive"))
      (node (ref "IC6") (pin "5") (pinfunction "+IN_5") (pintype "input"))
    )
    (net (code "40") (name "Net-(IC6B--IN)") (class "Default")
      (node (ref "IC6") (pin "6") (pinfunction "-IN_6") (pintype "input"))
      (node (ref "IC6") (pin "7") (pinfunction "OUT_7") (pintype "output"))
      (node (ref "R39P1") (pin "1") (pinfunction "P_1") (pintype "passive"))
    )
    (net (code "41") (name "Net-(IC7-+IN)") (class "Default")
      (node (ref "C4") (pin "2") (pinfunction "2_2") (pintype "passive"))
      (node (ref "IC7") (pin "3") (pinfunction "+IN_3") (pintype "input"))
      (node (ref "R29") (pin "1") (pinfunction "1_1") (pintype "passive"))
      (node (ref "R68") (pin "1") (pinfunction "1_1") (pintype "passive"))
    )
    (net (code "42") (name "Net-(IC7--IN)") (class "Default")
      (node (ref "IC7") (pin "2") (pinfunction "-IN_2") (pintype "input"))
      (node (ref "R35") (pin "2") (pinfunction "2_2") (pintype "passive"))
      (node (ref "R40") (pin "2") (pinfunction "2_2") (pintype "passive"))
    )
    (net (code "43") (name "Net-(IC7-OUT)") (class "Default")
      (node (ref "C4") (pin "1") (pinfunction "1_1") (pintype "passive"))
      (node (ref "IC7") (pin "6") (pinfunction "OUT_6") (pintype "output"))
      (node (ref "R36") (pin "1") (pinfunction "1_1") (pintype "passive"))
      (node (ref "R68") (pin "2") (pinfunction "2_2") (pintype "passive"))
    )
    (net (code "44") (name "Net-(LIN-P)") (class "Default")
      (node (ref "LIN") (pin "1") (pinfunction "P_1") (pintype "passive"))
      (node (ref "R30") (pin "2") (pinfunction "2_2") (pintype "passive"))
      (node (ref "R31") (pin "1") (pinfunction "1_1") (pintype "passive"))
    )
    (net (code "45") (name "Net-(PWM-P)") (class "Default")
      (node (ref "PWM") (pin "1") (pinfunction "P_1") (pintype "passive"))
      (node (ref "R40") (pin "1") (pinfunction "1_1") (pintype "passive"))
      (node (ref "R67") (pin "1") (pinfunction "1_1") (pintype "passive"))
    )
    (net (code "46") (name "Net-(Q2-G)") (class "Default")
      (node (ref "Q2") (pin "1") (pinfunction "G_1") (pintype "passive"))
      (node (ref "R50") (pin "2") (pinfunction "2_2") (pintype "passive"))
    )
    (net (code "47") (name "Net-(R2P1-P)") (class "Default")
      (node (ref "R2P1") (pin "1") (pinfunction "P_1") (pintype "passive"))
      (node (ref "R71") (pin "1") (pinfunction "1_1") (pintype "passive"))
    )
    (net (code "48") (name "Net-(R2P2-P)") (class "Default")
      (node (ref "R10") (pin "1") (pinfunction "1_1") (pintype "passive"))
      (node (ref "R2P2") (pin "1") (pinfunction "P_1") (pintype "passive"))
    )
    (net (code "49") (name "Net-(R2P3-P)") (class "Default")
      (node (ref "R2P3") (pin "1") (pinfunction "P_1") (pintype "passive"))
      (node (ref "R65") (pin "1") (pinfunction "1_1") (pintype "passive"))
    )
    (net (code "50") (name "Net-(R3P1-P)") (class "Default")
      (node (ref "R3P1") (pin "1") (pinfunction "P_1") (pintype "passive"))
      (node (ref "R56") (pin "2") (pinfunction "2_2") (pintype "passive"))
    )
    (net (code "51") (name "Net-(R3P2-P)") (class "Default")
      (node (ref "R3P2") (pin "1") (pinfunction "P_1") (pintype "passive"))
      (node (ref "R8") (pin "1") (pinfunction "1_1") (pintype "passive"))
    )
    (net (code "52") (name "Net-(R3P3-P)") (class "Default")
      (node (ref "R3P3") (pin "1") (pinfunction "P_1") (pintype "passive"))
      (node (ref "R57") (pin "2") (pinfunction "2_2") (pintype "passive"))
    )
    (net (code "53") (name "Net-(R5-E)") (class "Default")
      (node (ref "R5") (pin "3") (pinfunction "E_3") (pintype "passive"))
      (node (ref "R6") (pin "1") (pinfunction "1_1") (pintype "passive"))
    )
    (net (code "54") (name "Net-(R7-E)") (class "Default")
      (node (ref "R1") (pin "1") (pinfunction "1_1") (pintype "passive"))
      (node (ref "R7") (pin "3") (pinfunction "E_3") (pintype "passive"))
    )
    (net (code "55") (name "Net-(R11-E)") (class "Default")
      (node (ref "R11") (pin "2") (pinfunction "S_2") (pintype "passive"))
      (node (ref "R11") (pin "3") (pinfunction "E_3") (pintype "passive"))
      (node (ref "R9") (pin "1") (pinfunction "1_1") (pintype "passive"))
    )
    (net (code "56") (name "Net-(R16-A)") (class "Default")
      (node (ref "R16") (pin "1") (pinfunction "A_1") (pintype "passive"))
      (node (ref "R19") (pin "2") (pinfunction "2_2") (pintype "passive"))
    )
    (net (code "57") (name "Net-(R39P2-P)") (class "Default")
      (node (ref "R35") (pin "1") (pinfunction "1_1") (pintype "passive"))
      (node (ref "R39P2") (pin "1") (pinfunction "P_1") (pintype "passive"))
    )
    (net (code "58") (name "Net-(R59-E)") (class "Default")
      (node (ref "R44") (pin "2") (pinfunction "2_2") (pintype "passive"))
      (node (ref "R59") (pin "2") (pinfunction "S_2") (pintype "passive"))
      (node (ref "R59") (pin "3") (pinfunction "E_3") (pintype "passive"))
    )
    (net (code "59") (name "Net-(R60-S)") (class "Default")
      (node (ref "R60") (pin "2") (pinfunction "S_2") (pintype "passive"))
      (node (ref "R61") (pin "2") (pinfunction "2_2") (pintype "passive"))
    )
    (net (code "60") (name "Net-(R64-A)") (class "Default")
      (node (ref "R48") (pin "1") (pinfunction "1_1") (pintype "passive"))
      (node (ref "R64") (pin "1") (pinfunction "A_1") (pintype "passive"))
      (node (ref "R64") (pin "2") (pinfunction "S_2") (pintype "passive"))
    )
    (net (code "61") (name "Net-(RMP-P)") (class "Default")
      (node (ref "R26") (pin "2") (pinfunction "2_2") (pintype "passive"))
      (node (ref "RMP") (pin "1") (pinfunction "P_1") (pintype "passive"))
    )
    (net (code "62") (name "Net-(SIN-P)") (class "Default")
      (node (ref "R49") (pin "1") (pinfunction "1_1") (pintype "passive"))
      (node (ref "SIN") (pin "1") (pinfunction "P_1") (pintype "passive"))
    )
    (net (code "63") (name "Net-(SQR-P)") (class "Default")
      (node (ref "R36") (pin "2") (pinfunction "2_2") (pintype "passive"))
      (node (ref "R41") (pin "1") (pinfunction "1_1") (pintype "passive"))
      (node (ref "SQR") (pin "1") (pinfunction "P_1") (pintype "passive"))
    )
    (net (code "64") (name "Net-(SYNC-P)") (class "Default")
      (node (ref "C5") (pin "1") (pinfunction "1_1") (pintype "passive"))
      (node (ref "R66") (pin "1") (pinfunction "1_1") (pintype "passive"))
      (node (ref "SYNC") (pin "1") (pinfunction "P_1") (pintype "passive"))
    )
    (net (code "65") (name "Net-(TRI-P)") (class "Default")
      (node (ref "R22") (pin "2") (pinfunction "2_2") (pintype "passive"))
      (node (ref "TRI") (pin "1") (pinfunction "P_1") (pintype "passive"))
    )
    (net (code "66") (name "RAW") (class "Default")
      (node (ref "C6") (pin "2") (pinfunction "2_2") (pintype "passive"))
      (node (ref "IC2") (pin "1") (pinfunction "OUT_1") (pintype "output"))
      (node (ref "Q2") (pin "2") (pinfunction "S_2") (pintype "passive"))
      (node (ref "R12") (pin "1") (pinfunction "1_1") (pintype "passive"))
      (node (ref "R42") (pin "2") (pinfunction "2_2") (pintype "passive"))
    )
    (net (code "67") (name "unconnected-(IC3-NC1-Pad4)") (class "Default")
      (node (ref "IC3") (pin "4") (pinfunction "NC1_4") (pintype "bidirectional"))
    )
    (net (code "68") (name "unconnected-(IC3-NC2-Pad5)") (class "Default")
      (node (ref "IC3") (pin "5") (pinfunction "NC2_5") (pintype "bidirectional"))
    )
    (net (code "69") (name "unconnected-(IC5A-ID-Pad2)") (class "Default")
      (node (ref "IC5") (pin "2") (pinfunction "ID_2") (pintype "bidirectional"))
    )
    (net (code "70") (name "unconnected-(IC5B-IABC-Pad16)") (class "Default")
      (node (ref "IC5") (pin "16") (pinfunction "IABC_16") (pintype "bidirectional"))
    )
    (net (code "71") (name "unconnected-(IC5B-ID-Pad15)") (class "Default")
      (node (ref "IC5") (pin "15") (pinfunction "ID_15") (pintype "bidirectional"))
    )
    (net (code "72") (name "unconnected-(IC5B-OUT-Pad12)") (class "Default")
      (node (ref "IC5") (pin "12") (pinfunction "OUT_12") (pintype "bidirectional"))
    )
    (net (code "73") (name "unconnected-(IC5D-IN-Pad10)") (class "Default")
      (node (ref "IC5") (pin "10") (pinfunction "IN_10") (pintype "bidirectional"))
    )
    (net (code "74") (name "unconnected-(IC5D-OUT-Pad9)") (class "Default")
      (node (ref "IC5") (pin "9") (pinfunction "OUT_9") (pintype "bidirectional"))
    )
    (net (code "75") (name "unconnected-(IC7-ON1-Pad1)") (class "Default")
      (node (ref "IC7") (pin "1") (pinfunction "ON1_1") (pintype "passive"))
    )
    (net (code "76") (name "unconnected-(IC7-ON2-Pad5)") (class "Default")
      (node (ref "IC7") (pin "5") (pinfunction "ON2_5") (pintype "passive"))
    )
    (net (code "77") (name "unconnected-(IC7-OPT-Pad8)") (class "Default")
      (node (ref "IC7") (pin "8") (pinfunction "OPT_8") (pintype "passive"))
    )
  )
)
